# Part04_MT7688_Power.net
KiCad netlist of a schematic drawn in Altium Designer
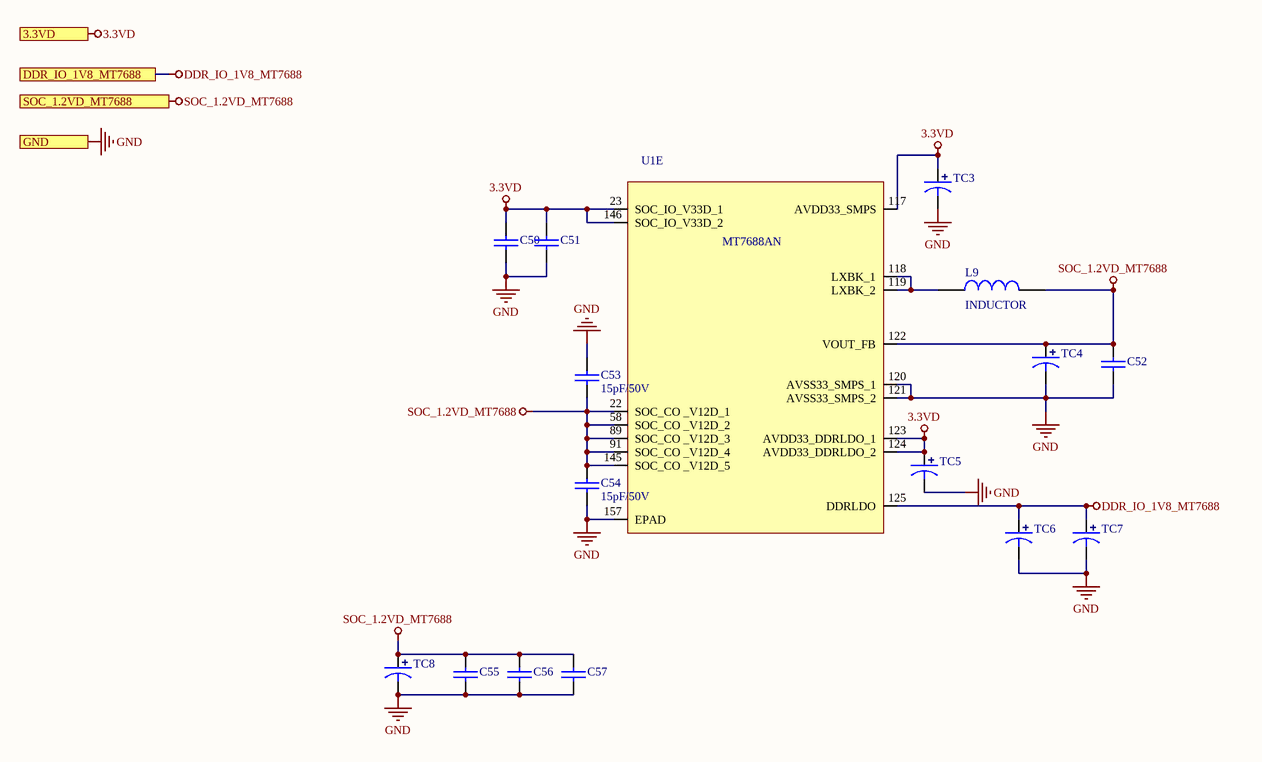
[diagram p0: Part04_MT7688_Power.SchDoc]

(export (version "E")
  (design (tool "Eeschema 10.0.6"))
  (components
    (comp (ref "C50")
      (value "0.1uF/16V")
      (footprint "0402C")
      (description "无极性电容")
      (libsource (lib "电容") (part "CAP"))
    )
    (comp (ref "C51")
      (value "0.1uF/16V")
      (footprint "0402C")
      (description "无极性电容")
      (libsource (lib "电容") (part "CAP"))
    )
    (comp (ref "C52")
      (value "0.1uF/16V")
      (footprint "0402C")
      (description "无极性电容")
      (libsource (lib "电容") (part "CAP"))
    )
    (comp (ref "C53")
      (value "15pF/50V")
      (footprint "0402C")
      (description "无极性电容")
      (libsource (lib "电容") (part "CAP"))
    )
    (comp (ref "C54")
      (value "15pF/50V")
      (footprint "0402C")
      (description "无极性电容")
      (libsource (lib "电容") (part "CAP"))
    )
    (comp (ref "C55")
      (value "0.1uF/16V")
      (footprint "0402C")
      (description "无极性电容")
      (libsource (lib "电容") (part "CAP"))
    )
    (comp (ref "C56")
      (value "0.1uF/16V")
      (footprint "0402C")
      (description "无极性电容")
      (libsource (lib "电容") (part "CAP"))
    )
    (comp (ref "C57")
      (value "0.1uF/16V")
      (footprint "0402C")
      (description "无极性电容")
      (libsource (lib "电容") (part "CAP"))
    )
    (comp (ref "L9") (value "INDUCTOR") (footprint "CD31") (libsource (lib "电感") (part "INDUCTOR")))
    (comp (ref "TC3")
      (value "2.2uF/6.3V")
      (footprint "TAJ-A/3216")
      (description "钽电容")
      (libsource (lib "电容") (part "TCAP"))
    )
    (comp (ref "TC4")
      (value "10uF/6.3V")
      (footprint "TAJ-A/3216")
      (description "钽电容")
      (libsource (lib "电容") (part "TCAP"))
    )
    (comp (ref "TC5")
      (value "10uF/6.3V")
      (footprint "TAJ-A/3216")
      (description "钽电容")
      (libsource (lib "电容") (part "TCAP"))
    )
    (comp (ref "TC6")
      (value "2.2uF/6.3V")
      (footprint "TAJ-A/3216")
      (description "钽电容")
      (libsource (lib "电容") (part "TCAP"))
    )
    (comp (ref "TC7")
      (value "4.7uF/6.3V")
      (footprint "TAJ-A/3216")
      (description "钽电容")
      (libsource (lib "电容") (part "TCAP"))
    )
    (comp (ref "TC8")
      (value "4.7uF/6.3V")
      (footprint "TAJ-A/3216")
      (description "钽电容")
      (libsource (lib "电容") (part "TCAP"))
    )
    (comp (ref "U1")
      (value "MT7688AN")
      (footprint "MT7628AN$2F$DRQFN156$2F$SMD$2F$P0.5$2F$12X12")
      (libsource (lib "MT7688_Lib") (part "MT7688AN"))
    )
  )
  (nets
    (net (code "1") (name "3.3VD") (class "Default")
      (node (ref "C50") (pin "1") (pinfunction "1_1") (pintype "passive"))
      (node (ref "C51") (pin "1") (pinfunction "1_1") (pintype "passive"))
      (node (ref "TC3") (pin "1") (pinfunction "1_1") (pintype "passive"))
      (node (ref "TC5") (pin "1") (pinfunction "1_1") (pintype "passive"))
      (node (ref "U1") (pin "117") (pinfunction "AVDD33_SMPS_117") (pintype "power_in"))
      (node (ref "U1") (pin "123") (pinfunction "AVDD33_DDRLDO_1_123") (pintype "power_in"))
      (node (ref "U1") (pin "124") (pinfunction "AVDD33_DDRLDO_2_124") (pintype "power_in"))
      (node (ref "U1") (pin "146") (pinfunction "SOC_IO_V33D_2_146") (pintype "power_in"))
      (node (ref "U1") (pin "23") (pinfunction "SOC_IO_V33D_1_23") (pintype "power_in"))
    )
    (net (code "2") (name "DDR_IO_1V8_MT7688") (class "Default")
      (node (ref "TC6") (pin "1") (pinfunction "1_1") (pintype "passive"))
      (node (ref "TC7") (pin "1") (pinfunction "1_1") (pintype "passive"))
      (node (ref "U1") (pin "125") (pinfunction "DDRLDO_125") (pintype "power_in"))
    )
    (net (code "3") (name "GND") (class "Default")
      (node (ref "C50") (pin "2") (pinfunction "2_2") (pintype "passive"))
      (node (ref "C51") (pin "2") (pinfunction "2_2") (pintype "passive"))
      (node (ref "C52") (pin "2") (pinfunction "2_2") (pintype "passive"))
      (node (ref "C53") (pin "1") (pinfunction "1_1") (pintype "passive"))
      (node (ref "C54") (pin "2") (pinfunction "2_2") (pintype "passive"))
      (node (ref "C55") (pin "2") (pinfunction "2_2") (pintype "passive"))
      (node (ref "C56") (pin "2") (pinfunction "2_2") (pintype "passive"))
      (node (ref "C57") (pin "2") (pinfunction "2_2") (pintype "passive"))
      (node (ref "TC3") (pin "2") (pinfunction "2_2") (pintype "passive"))
      (node (ref "TC4") (pin "2") (pinfunction "2_2") (pintype "passive"))
      (node (ref "TC5") (pin "2") (pinfunction "2_2") (pintype "passive"))
      (node (ref "TC6") (pin "2") (pinfunction "2_2") (pintype "passive"))
      (node (ref "TC7") (pin "2") (pinfunction "2_2") (pintype "passive"))
      (node (ref "TC8") (pin "2") (pinfunction "2_2") (pintype "passive"))
      (node (ref "U1") (pin "120") (pinfunction "AVSS33_SMPS_1_120") (pintype "power_in"))
      (node (ref "U1") (pin "121") (pinfunction "AVSS33_SMPS_2_121") (pintype "power_in"))
      (node (ref "U1") (pin "157") (pinfunction "EPAD_157") (pintype "power_in"))
    )
    (net (code "4") (name "Net-(U1E-LXBK_1)") (class "Default")
      (node (ref "L9") (pin "1") (pinfunction "1_1") (pintype "passive"))
      (node (ref "U1") (pin "118") (pinfunction "LXBK_1_118") (pintype "power_in"))
      (node (ref "U1") (pin "119") (pinfunction "LXBK_2_119") (pintype "power_in"))
    )
    (net (code "5") (name "SOC_1.2VD_MT7688") (class "Default")
      (node (ref "C52") (pin "1") (pinfunction "1_1") (pintype "passive"))
      (node (ref "C53") (pin "2") (pinfunction "2_2") (pintype "passive"))
      (node (ref "C54") (pin "1") (pinfunction "1_1") (pintype "passive"))
      (node (ref "C55") (pin "1") (pinfunction "1_1") (pintype "passive"))
      (node (ref "C56") (pin "1") (pinfunction "1_1") (pintype "passive"))
      (node (ref "C57") (pin "1") (pinfunction "1_1") (pintype "passive"))
      (node (ref "L9") (pin "2") (pinfunction "2_2") (pintype "passive"))
      (node (ref "TC4") (pin "1") (pinfunction "1_1") (pintype "passive"))
      (node (ref "TC8") (pin "1") (pinfunction "1_1") (pintype "passive"))
      (node (ref "U1") (pin "122") (pinfunction "VOUT_FB_122") (pintype "power_in"))
      (node (ref "U1") (pin "145") (pinfunction "SOC_CO__V12D_5_145") (pintype "power_in"))
      (node (ref "U1") (pin "22") (pinfunction "SOC_CO__V12D_1_22") (pintype "power_in"))
      (node (ref "U1") (pin "58") (pinfunction "SOC_CO__V12D_2_58") (pintype "power_in"))
      (node (ref "U1") (pin "89") (pinfunction "SOC_CO__V12D_3_89") (pintype "power_in"))
      (node (ref "U1") (pin "91") (pinfunction "SOC_CO__V12D_4_91") (pintype "power_in"))
    )
  )
)
